# Ethernet2.net
KiCad netlist of a schematic drawn in Altium Designer
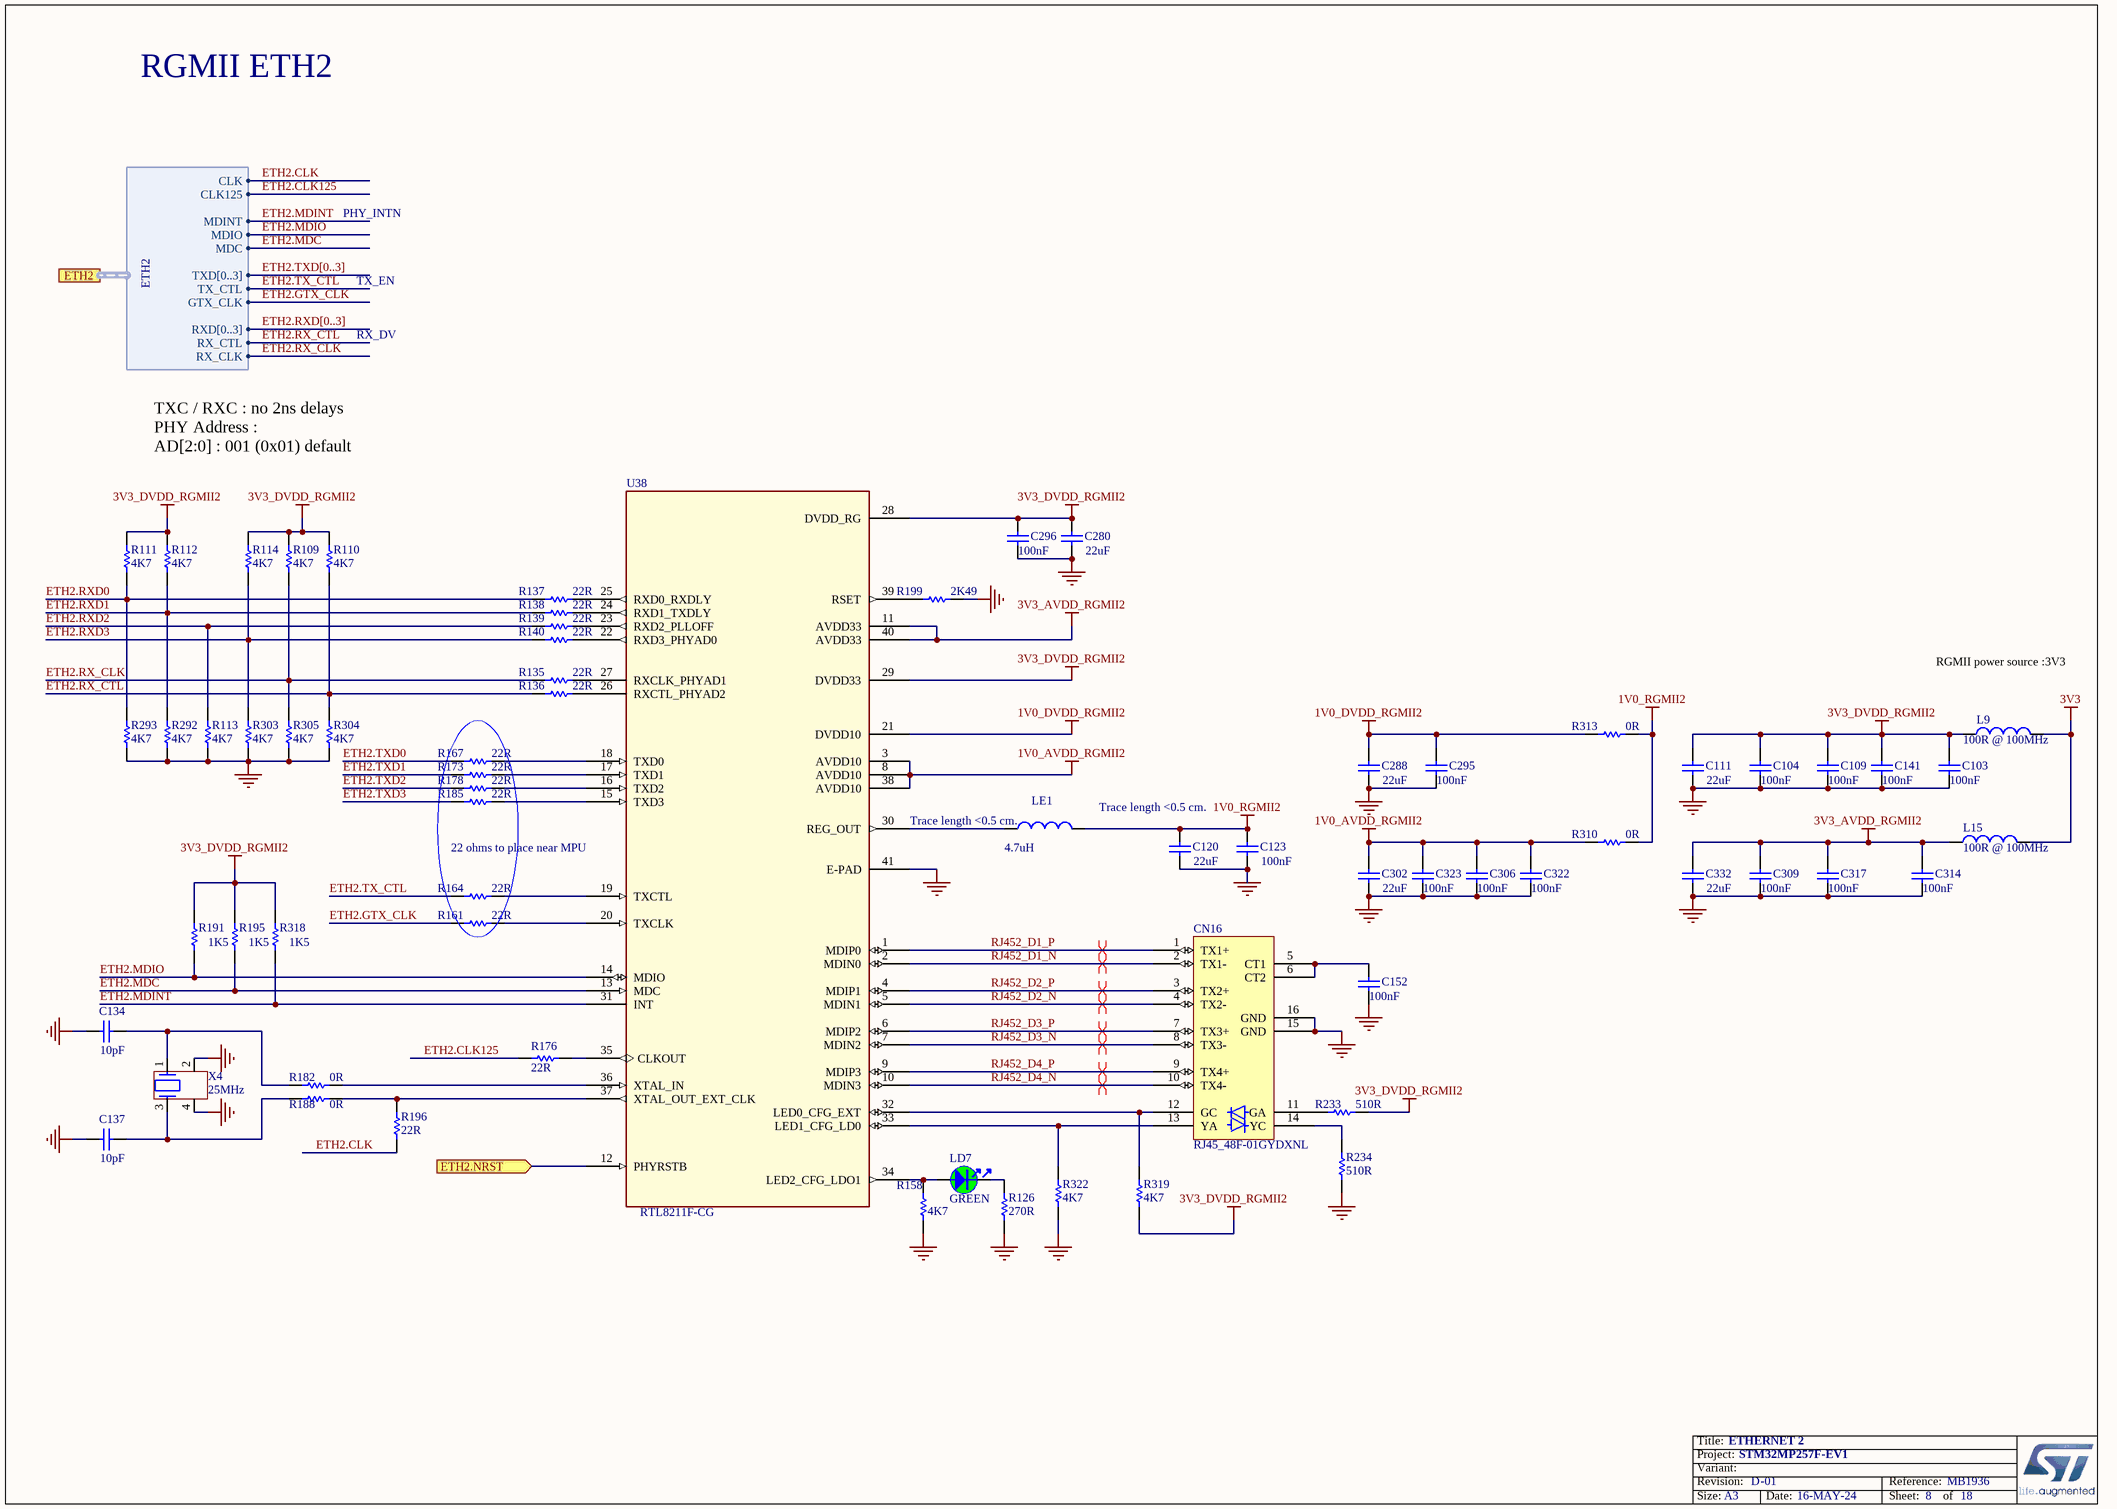
[diagram p0: Ethernet2.SchDoc]

(export (version "E")
  (design (tool "Eeschema 10.0.6"))
  (components
    (comp (ref "C103")
      (value "100nF")
      (footprint "MCD_PARTS:C0402")
      (description "Capacitor,100nF,16V,X7R,10%,0402")
      (fields
        (field (name "INTERNAL_PART_NUMBER") "MCD-00006")
        (field (name "MANUFACTURER_PART_NUMBER") "CC0402KRX7R7BB104")
        (field (name "PROVIDED_BY") "SUBCO")
      )
      (libsource (lib "MCD_PARTS_database") (part "Capacitor"))
    )
    (comp (ref "C104")
      (value "100nF")
      (footprint "MCD_PARTS:C0402")
      (description "Capacitor,100nF,16V,X7R,10%,0402")
      (fields
        (field (name "INTERNAL_PART_NUMBER") "MCD-00006")
        (field (name "MANUFACTURER_PART_NUMBER") "CC0402KRX7R7BB104")
        (field (name "PROVIDED_BY") "SUBCO")
      )
      (libsource (lib "MCD_PARTS_database") (part "Capacitor"))
    )
    (comp (ref "C109")
      (value "100nF")
      (footprint "MCD_PARTS:C0402")
      (description "Capacitor,100nF,16V,X7R,10%,0402")
      (fields
        (field (name "INTERNAL_PART_NUMBER") "MCD-00006")
        (field (name "MANUFACTURER_PART_NUMBER") "CC0402KRX7R7BB104")
        (field (name "PROVIDED_BY") "SUBCO")
      )
      (libsource (lib "MCD_PARTS_database") (part "Capacitor"))
    )
    (comp (ref "C111")
      (value "22uF")
      (footprint "MCD_PARTS:C0603")
      (description "Capacitor,22uF,6V3,X5R,20%,0603")
      (fields
        (field (name "INTERNAL_PART_NUMBER") "MCD-00100")
        (field (name "MANUFACTURER_PART_NUMBER") "GRM188R60J226MEA0J")
        (field (name "PROVIDED_BY") "SUBCO")
      )
      (libsource (lib "MCD_PARTS_database") (part "Capacitor"))
    )
    (comp (ref "C120")
      (value "22uF")
      (footprint "MCD_PARTS:C0603")
      (description "Capacitor,22uF,6V3,X5R,20%,0603")
      (fields
        (field (name "INTERNAL_PART_NUMBER") "MCD-00100")
        (field (name "MANUFACTURER_PART_NUMBER") "GRM188R60J226MEA0J")
        (field (name "PROVIDED_BY") "SUBCO")
      )
      (libsource (lib "MCD_PARTS_database") (part "Capacitor"))
    )
    (comp (ref "C123")
      (value "100nF")
      (footprint "MCD_PARTS:C0402")
      (description "Capacitor,100nF,16V,X7R,10%,0402")
      (fields
        (field (name "INTERNAL_PART_NUMBER") "MCD-00006")
        (field (name "MANUFACTURER_PART_NUMBER") "CC0402KRX7R7BB104")
        (field (name "PROVIDED_BY") "SUBCO")
      )
      (libsource (lib "MCD_PARTS_database") (part "Capacitor"))
    )
    (comp (ref "C134")
      (value "10pF")
      (footprint "MCD_PARTS:C0402")
      (description "Capacitor,10pF,50V,NPO,5%,0402")
      (fields
        (field (name "INTERNAL_PART_NUMBER") "MCD-00015")
        (field (name "MANUFACTURER_PART_NUMBER") "CC0402JRNPO9BN100")
        (field (name "PROVIDED_BY") "SUBCO")
      )
      (libsource (lib "MCD_PARTS_database") (part "Capacitor"))
    )
    (comp (ref "C137")
      (value "10pF")
      (footprint "MCD_PARTS:C0402")
      (description "Capacitor,10pF,50V,NPO,5%,0402")
      (fields
        (field (name "INTERNAL_PART_NUMBER") "MCD-00015")
        (field (name "MANUFACTURER_PART_NUMBER") "CC0402JRNPO9BN100")
        (field (name "PROVIDED_BY") "SUBCO")
      )
      (libsource (lib "MCD_PARTS_database") (part "Capacitor"))
    )
    (comp (ref "C141")
      (value "100nF")
      (footprint "MCD_PARTS:C0402")
      (description "Capacitor,100nF,16V,X7R,10%,0402")
      (fields
        (field (name "INTERNAL_PART_NUMBER") "MCD-00006")
        (field (name "MANUFACTURER_PART_NUMBER") "CC0402KRX7R7BB104")
        (field (name "PROVIDED_BY") "SUBCO")
      )
      (libsource (lib "MCD_PARTS_database") (part "Capacitor"))
    )
    (comp (ref "C152")
      (value "100nF")
      (footprint "MCD_PARTS:C0402")
      (description "Capacitor,100nF,16V,X7R,10%,0402")
      (fields
        (field (name "INTERNAL_PART_NUMBER") "MCD-00006")
        (field (name "MANUFACTURER_PART_NUMBER") "CC0402KRX7R7BB104")
        (field (name "PROVIDED_BY") "SUBCO")
      )
      (libsource (lib "MCD_PARTS_database") (part "Capacitor"))
    )
    (comp (ref "C280")
      (value "22uF")
      (footprint "MCD_PARTS:C0603")
      (description "Capacitor,22uF,6V3,X5R,20%,0603")
      (fields
        (field (name "INTERNAL_PART_NUMBER") "MCD-00100")
        (field (name "MANUFACTURER_PART_NUMBER") "GRM188R60J226MEA0J")
        (field (name "PROVIDED_BY") "SUBCO")
      )
      (libsource (lib "MCD_PARTS_database") (part "Capacitor"))
    )
    (comp (ref "C288")
      (value "22uF")
      (footprint "MCD_PARTS:C0603")
      (description "Capacitor,22uF,6V3,X5R,20%,0603")
      (fields
        (field (name "INTERNAL_PART_NUMBER") "MCD-00100")
        (field (name "MANUFACTURER_PART_NUMBER") "GRM188R60J226MEA0J")
        (field (name "PROVIDED_BY") "SUBCO")
      )
      (libsource (lib "MCD_PARTS_database") (part "Capacitor"))
    )
    (comp (ref "C295")
      (value "100nF")
      (footprint "MCD_PARTS:C0402")
      (description "Capacitor,100nF,16V,X7R,10%,0402")
      (fields
        (field (name "INTERNAL_PART_NUMBER") "MCD-00006")
        (field (name "MANUFACTURER_PART_NUMBER") "CC0402KRX7R7BB104")
        (field (name "PROVIDED_BY") "SUBCO")
      )
      (libsource (lib "MCD_PARTS_database") (part "Capacitor"))
    )
    (comp (ref "C296")
      (value "100nF")
      (footprint "MCD_PARTS:C0402")
      (description "Capacitor,100nF,16V,X7R,10%,0402")
      (fields
        (field (name "INTERNAL_PART_NUMBER") "MCD-00006")
        (field (name "MANUFACTURER_PART_NUMBER") "CC0402KRX7R7BB104")
        (field (name "PROVIDED_BY") "SUBCO")
      )
      (libsource (lib "MCD_PARTS_database") (part "Capacitor"))
    )
    (comp (ref "C302")
      (value "22uF")
      (footprint "MCD_PARTS:C0603")
      (description "Capacitor,22uF,6V3,X5R,20%,0603")
      (fields
        (field (name "INTERNAL_PART_NUMBER") "MCD-00100")
        (field (name "MANUFACTURER_PART_NUMBER") "GRM188R60J226MEA0J")
        (field (name "PROVIDED_BY") "SUBCO")
      )
      (libsource (lib "MCD_PARTS_database") (part "Capacitor"))
    )
    (comp (ref "C306")
      (value "100nF")
      (footprint "MCD_PARTS:C0402")
      (description "Capacitor,100nF,16V,X7R,10%,0402")
      (fields
        (field (name "INTERNAL_PART_NUMBER") "MCD-00006")
        (field (name "MANUFACTURER_PART_NUMBER") "CC0402KRX7R7BB104")
        (field (name "PROVIDED_BY") "SUBCO")
      )
      (libsource (lib "MCD_PARTS_database") (part "Capacitor"))
    )
    (comp (ref "C309")
      (value "100nF")
      (footprint "MCD_PARTS:C0402")
      (description "Capacitor,100nF,16V,X7R,10%,0402")
      (fields
        (field (name "INTERNAL_PART_NUMBER") "MCD-00006")
        (field (name "MANUFACTURER_PART_NUMBER") "CC0402KRX7R7BB104")
        (field (name "PROVIDED_BY") "SUBCO")
      )
      (libsource (lib "MCD_PARTS_database") (part "Capacitor"))
    )
    (comp (ref "C314")
      (value "100nF")
      (footprint "MCD_PARTS:C0402")
      (description "Capacitor,100nF,16V,X7R,10%,0402")
      (fields
        (field (name "INTERNAL_PART_NUMBER") "MCD-00006")
        (field (name "MANUFACTURER_PART_NUMBER") "CC0402KRX7R7BB104")
        (field (name "PROVIDED_BY") "SUBCO")
      )
      (libsource (lib "MCD_PARTS_database") (part "Capacitor"))
    )
    (comp (ref "C317")
      (value "100nF")
      (footprint "MCD_PARTS:C0402")
      (description "Capacitor,100nF,16V,X7R,10%,0402")
      (fields
        (field (name "INTERNAL_PART_NUMBER") "MCD-00006")
        (field (name "MANUFACTURER_PART_NUMBER") "CC0402KRX7R7BB104")
        (field (name "PROVIDED_BY") "SUBCO")
      )
      (libsource (lib "MCD_PARTS_database") (part "Capacitor"))
    )
    (comp (ref "C322")
      (value "100nF")
      (footprint "MCD_PARTS:C0402")
      (description "Capacitor,100nF,16V,X7R,10%,0402")
      (fields
        (field (name "INTERNAL_PART_NUMBER") "MCD-00006")
        (field (name "MANUFACTURER_PART_NUMBER") "CC0402KRX7R7BB104")
        (field (name "PROVIDED_BY") "SUBCO")
      )
      (libsource (lib "MCD_PARTS_database") (part "Capacitor"))
    )
    (comp (ref "C323")
      (value "100nF")
      (footprint "MCD_PARTS:C0402")
      (description "Capacitor,100nF,16V,X7R,10%,0402")
      (fields
        (field (name "INTERNAL_PART_NUMBER") "MCD-00006")
        (field (name "MANUFACTURER_PART_NUMBER") "CC0402KRX7R7BB104")
        (field (name "PROVIDED_BY") "SUBCO")
      )
      (libsource (lib "MCD_PARTS_database") (part "Capacitor"))
    )
    (comp (ref "C332")
      (value "22uF")
      (footprint "MCD_PARTS:C0603")
      (description "Capacitor,22uF,6V3,X5R,20%,0603")
      (fields
        (field (name "INTERNAL_PART_NUMBER") "MCD-00100")
        (field (name "MANUFACTURER_PART_NUMBER") "GRM188R60J226MEA0J")
        (field (name "PROVIDED_BY") "SUBCO")
      )
      (libsource (lib "MCD_PARTS_database") (part "Capacitor"))
    )
    (comp (ref "CN16")
      (value "RJ45_48F-01GYDXNL")
      (footprint "MCD_PARTS:CON_RJ45_YD_48F-01GYDXNL_LED-P")
      (description "Connector_RJ45, led pull down, T= 13.84mm")
      (fields
        (field (name "INTERNAL_PART_NUMBER") "MCD-01129")
        (field (name "MANUFACTURER_PART_NUMBER") "48F-01GYDXNL")
      )
      (libsource (lib "MCD_PARTS_database") (part "RJ45_48F_01GYDXNL_LPD"))
    )
    (comp (ref "L9")
      (value "100R @ 100MHz")
      (footprint "MCD_PARTS:FIL_0603_H0P65")
      (description "Ferrite bead 100R 2A 0603")
      (fields
        (field (name "INTERNAL_PART_NUMBER") "MCD-00094")
        (field (name "MANUFACTURER_PART_NUMBER") "BLM18EG101TN1")
        (field (name "PROVIDED_BY") "SUBCO")
      )
      (libsource (lib "MCD_PARTS_database") (part "BEAD"))
    )
    (comp (ref "L15")
      (value "100R @ 100MHz")
      (footprint "MCD_PARTS:FIL_0603_H0P65")
      (description "Ferrite bead 100R 2A 0603")
      (fields
        (field (name "INTERNAL_PART_NUMBER") "MCD-00094")
        (field (name "MANUFACTURER_PART_NUMBER") "BLM18EG101TN1")
        (field (name "PROVIDED_BY") "SUBCO")
      )
      (libsource (lib "MCD_PARTS_database") (part "BEAD"))
    )
    (comp (ref "LD7")
      (value "GREEN")
      (footprint "MCD_PARTS:LED_0603_OSRAM_LG-Q396-PS-35_GREEN_1A2K_H0P4")
      (description "LED Green, 0603 SMD, Forward Voltage Typ=2V, Max=2.5V")
      (fields
        (field (name "INTERNAL_PART_NUMBER") "MCD-00588")
        (field (name "MANUFACTURER_PART_NUMBER") "LG Q396-PS-35")
        (field (name "PROVIDED_BY") "SUBCO")
      )
      (libsource (lib "MCD_PARTS_database") (part "LED_green"))
    )
    (comp (ref "LE1")
      (value "4.7uH")
      (footprint "MCD_PARTS:L1210_LQH")
      (description "FIXED IND 4.7UH 1A 180 MOHM 30% SMD")
      (fields
        (field (name "INTERNAL_PART_NUMBER") "MCD-00048")
        (field (name "MANUFACTURER_PART_NUMBER") "LQH32PN4R7NN0L")
        (field (name "PROVIDED_BY") "SUBCO")
      )
      (libsource (lib "MCD_PARTS_database") (part "Inductor"))
    )
    (comp (ref "R109")
      (value "4K7")
      (footprint "MCD_PARTS:R0402")
      (description "Resistor,4K7,0402,1%,1/16W")
      (fields
        (field (name "INTERNAL_PART_NUMBER") "MCD-00065")
        (field (name "MANUFACTURER_PART_NUMBER") "RC0402FR-074K7L")
        (field (name "PROVIDED_BY") "SUBCO")
      )
      (libsource (lib "MCD_PARTS_database") (part "Resistor"))
    )
    (comp (ref "R110")
      (value "4K7")
      (footprint "MCD_PARTS:R0402")
      (description "Resistor,4K7,0402,1%,1/16W")
      (fields
        (field (name "INTERNAL_PART_NUMBER") "MCD-00065")
        (field (name "MANUFACTURER_PART_NUMBER") "RC0402FR-074K7L")
        (field (name "PROVIDED_BY") "SUBCO")
      )
      (libsource (lib "MCD_PARTS_database") (part "Resistor"))
    )
    (comp (ref "R111")
      (value "4K7")
      (footprint "MCD_PARTS:R0402")
      (description "Resistor,4K7,0402,1%,1/16W")
      (fields
        (field (name "INTERNAL_PART_NUMBER") "MCD-00065")
        (field (name "MANUFACTURER_PART_NUMBER") "RC0402FR-074K7L")
        (field (name "PROVIDED_BY") "SUBCO")
      )
      (libsource (lib "MCD_PARTS_database") (part "Resistor"))
    )
    (comp (ref "R112")
      (value "4K7")
      (footprint "MCD_PARTS:R0402")
      (description "Resistor,4K7,0402,1%,1/16W")
      (fields
        (field (name "INTERNAL_PART_NUMBER") "MCD-00065")
        (field (name "MANUFACTURER_PART_NUMBER") "RC0402FR-074K7L")
        (field (name "PROVIDED_BY") "SUBCO")
      )
      (libsource (lib "MCD_PARTS_database") (part "Resistor"))
    )
    (comp (ref "R113")
      (value "4K7")
      (footprint "MCD_PARTS:R0402")
      (description "Resistor,4K7,0402,1%,1/16W")
      (fields
        (field (name "INTERNAL_PART_NUMBER") "MCD-00065")
        (field (name "MANUFACTURER_PART_NUMBER") "RC0402FR-074K7L")
        (field (name "PROVIDED_BY") "SUBCO")
      )
      (libsource (lib "MCD_PARTS_database") (part "Resistor"))
    )
    (comp (ref "R114")
      (value "4K7")
      (footprint "MCD_PARTS:R0402")
      (description "Resistor,4K7,0402,1%,1/16W")
      (fields
        (field (name "INTERNAL_PART_NUMBER") "MCD-00065")
        (field (name "MANUFACTURER_PART_NUMBER") "RC0402FR-074K7L")
        (field (name "PROVIDED_BY") "SUBCO")
      )
      (libsource (lib "MCD_PARTS_database") (part "Resistor"))
    )
    (comp (ref "R126")
      (value "270R")
      (footprint "MCD_PARTS:R0402")
      (description "Resistor,270R,0402,1%,1/16W")
      (fields
        (field (name "INTERNAL_PART_NUMBER") "MCD-00441")
        (field (name "MANUFACTURER_PART_NUMBER") "RC0402FR-07270RL")
        (field (name "PROVIDED_BY") "SUBCO")
      )
      (libsource (lib "MCD_PARTS_database") (part "Resistor"))
    )
    (comp (ref "R135")
      (value "22R")
      (footprint "MCD_PARTS:R0201_H0P23")
      (description "Resistor, 22R, 0201, +/-1%, 1/20W")
      (fields
        (field (name "INTERNAL_PART_NUMBER") "MCD-02978")
        (field (name "MANUFACTURER_PART_NUMBER") "RC0201FR-0722RL")
      )
      (libsource (lib "MCD_PARTS_database") (part "Resistor"))
    )
    (comp (ref "R136")
      (value "22R")
      (footprint "MCD_PARTS:R0201_H0P23")
      (description "Resistor, 22R, 0201, +/-1%, 1/20W")
      (fields
        (field (name "INTERNAL_PART_NUMBER") "MCD-02978")
        (field (name "MANUFACTURER_PART_NUMBER") "RC0201FR-0722RL")
      )
      (libsource (lib "MCD_PARTS_database") (part "Resistor"))
    )
    (comp (ref "R137")
      (value "22R")
      (footprint "MCD_PARTS:R0201_H0P23")
      (description "Resistor, 22R, 0201, +/-1%, 1/20W")
      (fields
        (field (name "INTERNAL_PART_NUMBER") "MCD-02978")
        (field (name "MANUFACTURER_PART_NUMBER") "RC0201FR-0722RL")
      )
      (libsource (lib "MCD_PARTS_database") (part "Resistor"))
    )
    (comp (ref "R138")
      (value "22R")
      (footprint "MCD_PARTS:R0201_H0P23")
      (description "Resistor, 22R, 0201, +/-1%, 1/20W")
      (fields
        (field (name "INTERNAL_PART_NUMBER") "MCD-02978")
        (field (name "MANUFACTURER_PART_NUMBER") "RC0201FR-0722RL")
      )
      (libsource (lib "MCD_PARTS_database") (part "Resistor"))
    )
    (comp (ref "R139")
      (value "22R")
      (footprint "MCD_PARTS:R0201_H0P23")
      (description "Resistor, 22R, 0201, +/-1%, 1/20W")
      (fields
        (field (name "INTERNAL_PART_NUMBER") "MCD-02978")
        (field (name "MANUFACTURER_PART_NUMBER") "RC0201FR-0722RL")
      )
      (libsource (lib "MCD_PARTS_database") (part "Resistor"))
    )
    (comp (ref "R140")
      (value "22R")
      (footprint "MCD_PARTS:R0201_H0P23")
      (description "Resistor, 22R, 0201, +/-1%, 1/20W")
      (fields
        (field (name "INTERNAL_PART_NUMBER") "MCD-02978")
        (field (name "MANUFACTURER_PART_NUMBER") "RC0201FR-0722RL")
      )
      (libsource (lib "MCD_PARTS_database") (part "Resistor"))
    )
    (comp (ref "R158")
      (value "4K7")
      (footprint "MCD_PARTS:R0402")
      (description "Resistor,4K7,0402,1%,1/16W")
      (fields
        (field (name "INTERNAL_PART_NUMBER") "MCD-00065")
        (field (name "MANUFACTURER_PART_NUMBER") "RC0402FR-074K7L")
        (field (name "PROVIDED_BY") "SUBCO")
      )
      (libsource (lib "MCD_PARTS_database") (part "Resistor"))
    )
    (comp (ref "R161")
      (value "22R")
      (footprint "MCD_PARTS:R0201_H0P23")
      (description "Resistor, 22R, 0201, +/-1%, 1/20W")
      (fields
        (field (name "INTERNAL_PART_NUMBER") "MCD-02978")
        (field (name "MANUFACTURER_PART_NUMBER") "RC0201FR-0722RL")
      )
      (libsource (lib "MCD_PARTS_database") (part "Resistor"))
    )
    (comp (ref "R164")
      (value "22R")
      (footprint "MCD_PARTS:R0201_H0P23")
      (description "Resistor, 22R, 0201, +/-1%, 1/20W")
      (fields
        (field (name "INTERNAL_PART_NUMBER") "MCD-02978")
        (field (name "MANUFACTURER_PART_NUMBER") "RC0201FR-0722RL")
      )
      (libsource (lib "MCD_PARTS_database") (part "Resistor"))
    )
    (comp (ref "R167")
      (value "22R")
      (footprint "MCD_PARTS:R0201_H0P23")
      (description "Resistor, 22R, 0201, +/-1%, 1/20W")
      (fields
        (field (name "INTERNAL_PART_NUMBER") "MCD-02978")
        (field (name "MANUFACTURER_PART_NUMBER") "RC0201FR-0722RL")
      )
      (libsource (lib "MCD_PARTS_database") (part "Resistor"))
    )
    (comp (ref "R173")
      (value "22R")
      (footprint "MCD_PARTS:R0201_H0P23")
      (description "Resistor, 22R, 0201, +/-1%, 1/20W")
      (fields
        (field (name "INTERNAL_PART_NUMBER") "MCD-02978")
        (field (name "MANUFACTURER_PART_NUMBER") "RC0201FR-0722RL")
      )
      (libsource (lib "MCD_PARTS_database") (part "Resistor"))
    )
    (comp (ref "R176")
      (value "22R")
      (footprint "MCD_PARTS:R0201_H0P23")
      (description "Resistor, 22R, 0201, +/-1%, 1/20W")
      (fields
        (field (name "INTERNAL_PART_NUMBER") "MCD-02978")
        (field (name "MANUFACTURER_PART_NUMBER") "RC0201FR-0722RL")
      )
      (libsource (lib "MCD_PARTS_database") (part "Resistor"))
    )
    (comp (ref "R178")
      (value "22R")
      (footprint "MCD_PARTS:R0201_H0P23")
      (description "Resistor, 22R, 0201, +/-1%, 1/20W")
      (fields
        (field (name "INTERNAL_PART_NUMBER") "MCD-02978")
        (field (name "MANUFACTURER_PART_NUMBER") "RC0201FR-0722RL")
      )
      (libsource (lib "MCD_PARTS_database") (part "Resistor"))
    )
    (comp (ref "R182")
      (value "0R")
      (footprint "MCD_PARTS:R0402")
      (description "Resistor,0R,0402,5%,1/16W")
      (fields
        (field (name "INTERNAL_PART_NUMBER") "MCD-00052")
        (field (name "MANUFACTURER_PART_NUMBER") "RC0402JR-070RL")
        (field (name "PROVIDED_BY") "SUBCO")
      )
      (libsource (lib "MCD_PARTS_database") (part "Resistor"))
    )
    (comp (ref "R185")
      (value "22R")
      (footprint "MCD_PARTS:R0201_H0P23")
      (description "Resistor, 22R, 0201, +/-1%, 1/20W")
      (fields
        (field (name "INTERNAL_PART_NUMBER") "MCD-02978")
        (field (name "MANUFACTURER_PART_NUMBER") "RC0201FR-0722RL")
      )
      (libsource (lib "MCD_PARTS_database") (part "Resistor"))
    )
    (comp (ref "R188")
      (value "0R")
      (footprint "MCD_PARTS:R0402")
      (description "Resistor,0R,0402,5%,1/16W")
      (fields
        (field (name "INTERNAL_PART_NUMBER") "MCD-00052")
        (field (name "MANUFACTURER_PART_NUMBER") "RC0402JR-070RL")
        (field (name "PROVIDED_BY") "SUBCO")
      )
      (libsource (lib "MCD_PARTS_database") (part "Resistor"))
    )
    (comp (ref "R191")
      (value "1K5")
      (footprint "MCD_PARTS:R0402")
      (description "Resistor,1K5,0402,1%,1/16W")
      (fields
        (field (name "INTERNAL_PART_NUMBER") "MCD-00068")
        (field (name "MANUFACTURER_PART_NUMBER") "RC0402FR-071K5L")
        (field (name "PROVIDED_BY") "SUBCO")
      )
      (libsource (lib "MCD_PARTS_database") (part "Resistor"))
    )
    (comp (ref "R195")
      (value "1K5")
      (footprint "MCD_PARTS:R0402")
      (description "Resistor,1K5,0402,1%,1/16W")
      (fields
        (field (name "INTERNAL_PART_NUMBER") "MCD-00068")
        (field (name "MANUFACTURER_PART_NUMBER") "RC0402FR-071K5L")
        (field (name "PROVIDED_BY") "SUBCO")
      )
      (libsource (lib "MCD_PARTS_database") (part "Resistor"))
    )
    (comp (ref "R196")
      (value "22R")
      (footprint "MCD_PARTS:R0201_H0P23")
      (description "Resistor, 22R, 0201, +/-1%, 1/20W")
      (fields
        (field (name "INTERNAL_PART_NUMBER") "MCD-02978")
        (field (name "MANUFACTURER_PART_NUMBER") "RC0201FR-0722RL")
      )
      (libsource (lib "MCD_PARTS_database") (part "Resistor"))
    )
    (comp (ref "R199")
      (value "2K49")
      (footprint "MCD_PARTS:R0402")
      (description "Resistor,2K49,0402,1%,1/16W")
      (fields
        (field (name "INTERNAL_PART_NUMBER") "MCD-00183")
        (field (name "MANUFACTURER_PART_NUMBER") "RC0402FR-072K49L")
        (field (name "PROVIDED_BY") "SUBCO")
      )
      (libsource (lib "MCD_PARTS_database") (part "Resistor"))
    )
    (comp (ref "R233")
      (value "510R")
      (footprint "MCD_PARTS:R0402")
      (description "Resistor,510R,0402,1%,1/16W")
      (fields
        (field (name "INTERNAL_PART_NUMBER") "MCD-00064")
        (field (name "MANUFACTURER_PART_NUMBER") "RC0402FR-07510RL")
        (field (name "PROVIDED_BY") "SUBCO")
      )
      (libsource (lib "MCD_PARTS_database") (part "Resistor"))
    )
    (comp (ref "R234")
      (value "510R")
      (footprint "MCD_PARTS:R0402")
      (description "Resistor,510R,0402,1%,1/16W")
      (fields
        (field (name "INTERNAL_PART_NUMBER") "MCD-00064")
        (field (name "MANUFACTURER_PART_NUMBER") "RC0402FR-07510RL")
        (field (name "PROVIDED_BY") "SUBCO")
      )
      (libsource (lib "MCD_PARTS_database") (part "Resistor"))
    )
    (comp (ref "R292")
      (value "4K7")
      (footprint "MCD_PARTS:R0402")
      (description "Resistor,4K7,0402,1%,1/16W")
      (fields
        (field (name "INTERNAL_PART_NUMBER") "MCD-00065")
        (field (name "MANUFACTURER_PART_NUMBER") "RC0402FR-074K7L")
        (field (name "PROVIDED_BY") "SUBCO")
      )
      (libsource (lib "MCD_PARTS_database") (part "Resistor"))
    )
    (comp (ref "R293")
      (value "4K7")
      (footprint "MCD_PARTS:R0402")
      (description "Resistor,4K7,0402,1%,1/16W")
      (fields
        (field (name "INTERNAL_PART_NUMBER") "MCD-00065")
        (field (name "MANUFACTURER_PART_NUMBER") "RC0402FR-074K7L")
        (field (name "PROVIDED_BY") "SUBCO")
      )
      (libsource (lib "MCD_PARTS_database") (part "Resistor"))
    )
    (comp (ref "R303")
      (value "4K7")
      (footprint "MCD_PARTS:R0402")
      (description "Resistor,4K7,0402,1%,1/16W")
      (fields
        (field (name "INTERNAL_PART_NUMBER") "MCD-00065")
        (field (name "MANUFACTURER_PART_NUMBER") "RC0402FR-074K7L")
        (field (name "PROVIDED_BY") "SUBCO")
      )
      (libsource (lib "MCD_PARTS_database") (part "Resistor"))
    )
    (comp (ref "R304")
      (value "4K7")
      (footprint "MCD_PARTS:R0402")
      (description "Resistor,4K7,0402,1%,1/16W")
      (fields
        (field (name "INTERNAL_PART_NUMBER") "MCD-00065")
        (field (name "MANUFACTURER_PART_NUMBER") "RC0402FR-074K7L")
        (field (name "PROVIDED_BY") "SUBCO")
      )
      (libsource (lib "MCD_PARTS_database") (part "Resistor"))
    )
    (comp (ref "R305")
      (value "4K7")
      (footprint "MCD_PARTS:R0402")
      (description "Resistor,4K7,0402,1%,1/16W")
      (fields
        (field (name "INTERNAL_PART_NUMBER") "MCD-00065")
        (field (name "MANUFACTURER_PART_NUMBER") "RC0402FR-074K7L")
        (field (name "PROVIDED_BY") "SUBCO")
      )
      (libsource (lib "MCD_PARTS_database") (part "Resistor"))
    )
    (comp (ref "R310")
      (value "0R")
      (footprint "MCD_PARTS:R0603")
      (description "Resistor,0R,0603,5%,1/10W")
      (fields
        (field (name "INTERNAL_PART_NUMBER") "MCD-00056")
        (field (name "MANUFACTURER_PART_NUMBER") "RC0603JR-070RL")
        (field (name "PROVIDED_BY") "SUBCO")
      )
      (libsource (lib "MCD_PARTS_database") (part "Resistor"))
    )
    (comp (ref "R313")
      (value "0R")
      (footprint "MCD_PARTS:R0603")
      (description "Resistor,0R,0603,5%,1/10W")
      (fields
        (field (name "INTERNAL_PART_NUMBER") "MCD-00056")
        (field (name "MANUFACTURER_PART_NUMBER") "RC0603JR-070RL")
        (field (name "PROVIDED_BY") "SUBCO")
      )
      (libsource (lib "MCD_PARTS_database") (part "Resistor"))
    )
    (comp (ref "R318")
      (value "1K5")
      (footprint "MCD_PARTS:R0402")
      (description "Resistor,1K5,0402,1%,1/16W")
      (fields
        (field (name "INTERNAL_PART_NUMBER") "MCD-00068")
        (field (name "MANUFACTURER_PART_NUMBER") "RC0402FR-071K5L")
        (field (name "PROVIDED_BY") "SUBCO")
      )
      (libsource (lib "MCD_PARTS_database") (part "Resistor"))
    )
    (comp (ref "R319")
      (value "4K7")
      (footprint "MCD_PARTS:R0402")
      (description "Resistor,4K7,0402,1%,1/16W")
      (fields
        (field (name "INTERNAL_PART_NUMBER") "MCD-00065")
        (field (name "MANUFACTURER_PART_NUMBER") "RC0402FR-074K7L")
        (field (name "PROVIDED_BY") "SUBCO")
      )
      (libsource (lib "MCD_PARTS_database") (part "Resistor"))
    )
    (comp (ref "R322")
      (value "4K7")
      (footprint "MCD_PARTS:R0402")
      (description "Resistor,4K7,0402,1%,1/16W")
      (fields
        (field (name "INTERNAL_PART_NUMBER") "MCD-00065")
        (field (name "MANUFACTURER_PART_NUMBER") "RC0402FR-074K7L")
        (field (name "PROVIDED_BY") "SUBCO")
      )
      (libsource (lib "MCD_PARTS_database") (part "Resistor"))
    )
    (comp (ref "U38")
      (value "RTL8211F-CG")
      (footprint "MCD_PARTS:ICC_QFN40-EPAD_5X5_P040")
      (description "10/100/1000M GIGABIT Ethernet Transceiver, QFN40 , SMPS version")
      (fields
        (field (name "INTERNAL_PART_NUMBER") "MCD-01130")
        (field (name "MANUFACTURER") "REALTEK")
        (field (name "PROVIDED_BY") "SUBCO")
      )
      (libsource (lib "MCD_PARTS_database") (part "RTL8211F-CG"))
    )
    (comp (ref "X4")
      (value "25MHz")
      (footprint "MCD_PARTS:CRY_NX3225HA_4P")
      (description "Crystal 25Mhz, 10pF, -+50PPM, SMD")
      (fields
        (field (name "INTERNAL_PART_NUMBER") "MCD-01463")
        (field (name "MANUFACTURER_PART_NUMBER") "NX3225GA-25MHZ-EXS00A-CG06750")
        (field (name "PROVIDED_BY") "SUBCO")
      )
      (libsource (lib "MCD_PARTS_database") (part "XTAL_4_PINS"))
    )
  )
  (nets
    (net (code "2") (name "/ETH2.CLK") (class "Default")
      (node (ref "R196") (pin "1") (pinfunction "1_1") (pintype "passive"))
    )
    (net (code "3") (name "/ETH2.CLK125") (class "Default")
      (node (ref "R176") (pin "1") (pinfunction "1_1") (pintype "passive"))
    )
    (net (code "4") (name "/ETH2.GTX_CLK") (class "Default")
      (node (ref "R161") (pin "1") (pinfunction "1_1") (pintype "passive"))
    )
    (net (code "5") (name "/ETH2.MDC") (class "Default")
      (node (ref "R195") (pin "1") (pinfunction "1_1") (pintype "passive"))
      (node (ref "U38") (pin "13") (pinfunction "MDC_13") (pintype "input"))
    )
    (net (code "6") (name "/ETH2.MDINT") (class "Default")
      (node (ref "R318") (pin "1") (pinfunction "1_1") (pintype "passive"))
      (node (ref "U38") (pin "31") (pinfunction "INT_31") (pintype "passive"))
    )
    (net (code "7") (name "/ETH2.MDIO") (class "Default")
      (node (ref "R191") (pin "1") (pinfunction "1_1") (pintype "passive"))
      (node (ref "U38") (pin "14") (pinfunction "MDIO_14") (pintype "bidirectional"))
    )
    (net (code "8") (name "/ETH2.NRST") (class "Default")
      (node (ref "U38") (pin "12") (pinfunction "PHYRSTB_12") (pintype "input"))
    )
    (net (code "9") (name "/ETH2.RXD0") (class "Default")
      (node (ref "R111") (pin "1") (pinfunction "1_1") (pintype "passive"))
      (node (ref "R137") (pin "1") (pinfunction "1_1") (pintype "passive"))
      (node (ref "R293") (pin "2") (pinfunction "2_2") (pintype "passive"))
    )
    (net (code "10") (name "/ETH2.RXD1") (class "Default")
      (node (ref "R112") (pin "1") (pinfunction "1_1") (pintype "passive"))
      (node (ref "R138") (pin "1") (pinfunction "1_1") (pintype "passive"))
      (node (ref "R292") (pin "2") (pinfunction "2_2") (pintype "passive"))
    )
    (net (code "11") (name "/ETH2.RXD2") (class "Default")
      (node (ref "R113") (pin "2") (pinfunction "2_2") (pintype "passive"))
      (node (ref "R139") (pin "1") (pinfunction "1_1") (pintype "passive"))
    )
    (net (code "12") (name "/ETH2.RXD3") (class "Default")
      (node (ref "R114") (pin "1") (pinfunction "1_1") (pintype "passive"))
      (node (ref "R140") (pin "1") (pinfunction "1_1") (pintype "passive"))
      (node (ref "R303") (pin "2") (pinfunction "2_2") (pintype "passive"))
    )
    (net (code "13") (name "/ETH2.RX_CLK") (class "Default")
      (node (ref "R109") (pin "1") (pinfunction "1_1") (pintype "passive"))
      (node (ref "R135") (pin "1") (pinfunction "1_1") (pintype "passive"))
      (node (ref "R305") (pin "2") (pinfunction "2_2") (pintype "passive"))
    )
    (net (code "14") (name "/ETH2.RX_CTL") (class "Default")
      (node (ref "R110") (pin "1") (pinfunction "1_1") (pintype "passive"))
      (node (ref "R136") (pin "1") (pinfunction "1_1") (pintype "passive"))
      (node (ref "R304") (pin "2") (pinfunction "2_2") (pintype "passive"))
    )
    (net (code "15") (name "/ETH2.TXD0") (class "Default")
      (node (ref "R167") (pin "1") (pinfunction "1_1") (pintype "passive"))
    )
    (net (code "16") (name "/ETH2.TXD1") (class "Default")
      (node (ref "R173") (pin "1") (pinfunction "1_1") (pintype "passive"))
    )
    (net (code "17") (name "/ETH2.TXD2") (class "Default")
      (node (ref "R178") (pin "1") (pinfunction "1_1") (pintype "passive"))
    )
    (net (code "18") (name "/ETH2.TXD3") (class "Default")
      (node (ref "R185") (pin "1") (pinfunction "1_1") (pintype "passive"))
    )
    (net (code "20") (name "/ETH2.TX_CTL") (class "Default")
      (node (ref "R164") (pin "1") (pinfunction "1_1") (pintype "passive"))
    )
    (net (code "22") (name "/RJ452_D1_N") (class "Default")
      (node (ref "CN16") (pin "2") (pinfunction "TX1-_2") (pintype "bidirectional"))
      (node (ref "U38") (pin "2") (pinfunction "MDIN0_2") (pintype "bidirectional"))
    )
    (net (code "23") (name "/RJ452_D1_P") (class "Default")
      (node (ref "CN16") (pin "1") (pinfunction "TX1+_1") (pintype "bidirectional"))
      (node (ref "U38") (pin "1") (pinfunction "MDIP0_1") (pintype "bidirectional"))
    )
    (net (code "24") (name "/RJ452_D2_N") (class "Default")
      (node (ref "CN16") (pin "4") (pinfunction "TX2-_4") (pintype "bidirectional"))
      (node (ref "U38") (pin "5") (pinfunction "MDIN1_5") (pintype "bidirectional"))
    )
    (net (code "25") (name "/RJ452_D2_P") (class "Default")
      (node (ref "CN16") (pin "3") (pinfunction "TX2+_3") (pintype "bidirectional"))
      (node (ref "U38") (pin "4") (pinfunction "MDIP1_4") (pintype "bidirectional"))
    )
    (net (code "26") (name "/RJ452_D3_N") (class "Default")
      (node (ref "CN16") (pin "8") (pinfunction "TX3-_8") (pintype "bidirectional"))
      (node (ref "U38") (pin "7") (pinfunction "MDIN2_7") (pintype "bidirectional"))
    )
    (net (code "27") (name "/RJ452_D3_P") (class "Default")
      (node (ref "CN16") (pin "7") (pinfunction "TX3+_7") (pintype "bidirectional"))
      (node (ref "U38") (pin "6") (pinfunction "MDIP2_6") (pintype "bidirectional"))
    )
    (net (code "28") (name "/RJ452_D4_N") (class "Default")
      (node (ref "CN16") (pin "10") (pinfunction "TX4-_10") (pintype "bidirectional"))
      (node (ref "U38") (pin "10") (pinfunction "MDIN3_10") (pintype "bidirectional"))
    )
    (net (code "29") (name "/RJ452_D4_P") (class "Default")
      (node (ref "CN16") (pin "9") (pinfunction "TX4+_9") (pintype "bidirectional"))
      (node (ref "U38") (pin "9") (pinfunction "MDIP3_9") (pintype "bidirectional"))
    )
    (net (code "31") (name "1V0_AVDD_RGMII2") (class "Default")
      (node (ref "C302") (pin "2") (pinfunction "2_2") (pintype "passive"))
      (node (ref "C306") (pin "2") (pinfunction "2_2") (pintype "passive"))
      (node (ref "C322") (pin "2") (pinfunction "2_2") (pintype "passive"))
      (node (ref "C323") (pin "2") (pinfunction "2_2") (pintype "passive"))
      (node (ref "R310") (pin "1") (pinfunction "1_1") (pintype "passive"))
      (node (ref "U38") (pin "3") (pinfunction "AVDD10_3") (pintype "power_in"))
      (node (ref "U38") (pin "38") (pinfunction "AVDD10_38") (pintype "power_in"))
      (node (ref "U38") (pin "8") (pinfunction "AVDD10_8") (pintype "power_in"))
    )
    (net (code "32") (name "1V0_DVDD_RGMII2") (class "Default")
      (node (ref "C288") (pin "2") (pinfunction "2_2") (pintype "passive"))
      (node (ref "C295") (pin "2") (pinfunction "2_2") (pintype "passive"))
      (node (ref "R313") (pin "1") (pinfunction "1_1") (pintype "passive"))
      (node (ref "U38") (pin "21") (pinfunction "DVDD10_21") (pintype "power_in"))
    )
    (net (code "33") (name "1V0_RGMII2") (class "Default")
      (node (ref "C120") (pin "2") (pinfunction "2_2") (pintype "passive"))
      (node (ref "C123") (pin "2") (pinfunction "2_2") (pintype "passive"))
      (node (ref "LE1") (pin "2") (pinfunction "2_2") (pintype "passive"))
      (node (ref "R310") (pin "2") (pinfunction "2_2") (pintype "passive"))
      (node (ref "R313") (pin "2") (pinfunction "2_2") (pintype "passive"))
    )
    (net (code "34") (name "3V3") (class "Default")
      (node (ref "L15") (pin "2") (pinfunction "2_2") (pintype "passive"))
      (node (ref "L9") (pin "2") (pinfunction "2_2") (pintype "passive"))
    )
    (net (code "35") (name "3V3_AVDD_RGMII2") (class "Default")
      (node (ref "C309") (pin "2") (pinfunction "2_2") (pintype "passive"))
      (node (ref "C314") (pin "2") (pinfunction "2_2") (pintype "passive"))
      (node (ref "C317") (pin "2") (pinfunction "2_2") (pintype "passive"))
      (node (ref "C332") (pin "2") (pinfunction "2_2") (pintype "passive"))
      (node (ref "L15") (pin "1") (pinfunction "1_1") (pintype "passive"))
      (node (ref "U38") (pin "11") (pinfunction "AVDD33_11") (pintype "power_in"))
      (node (ref "U38") (pin "40") (pinfunction "AVDD33_40") (pintype "power_in"))
    )
    (net (code "36") (name "3V3_DVDD_RGMII2") (class "Default")
      (node (ref "C103") (pin "2") (pinfunction "2_2") (pintype "passive"))
      (node (ref "C104") (pin "2") (pinfunction "2_2") (pintype "passive"))
      (node (ref "C109") (pin "2") (pinfunction "2_2") (pintype "passive"))
      (node (ref "C111") (pin "2") (pinfunction "2_2") (pintype "passive"))
      (node (ref "C141") (pin "2") (pinfunction "2_2") (pintype "passive"))
      (node (ref "C280") (pin "1") (pinfunction "1_1") (pintype "passive"))
      (node (ref "C296") (pin "2") (pinfunction "2_2") (pintype "passive"))
      (node (ref "L9") (pin "1") (pinfunction "1_1") (pintype "passive"))
      (node (ref "R109") (pin "2") (pinfunction "2_2") (pintype "passive"))
      (node (ref "R110") (pin "2") (pinfunction "2_2") (pintype "passive"))
      (node (ref "R111") (pin "2") (pinfunction "2_2") (pintype "passive"))
      (node (ref "R112") (pin "2") (pinfunction "2_2") (pintype "passive"))
      (node (ref "R114") (pin "2") (pinfunction "2_2") (pintype "passive"))
      (node (ref "R191") (pin "2") (pinfunction "2_2") (pintype "passive"))
      (node (ref "R195") (pin "2") (pinfunction "2_2") (pintype "passive"))
      (node (ref "R233") (pin "2") (pinfunction "2_2") (pintype "passive"))
      (node (ref "R318") (pin "2") (pinfunction "2_2") (pintype "passive"))
      (node (ref "R319") (pin "1") (pinfunction "1_1") (pintype "passive"))
      (node (ref "U38") (pin "28") (pinfunction "DVDD_RG_28") (pintype "power_in"))
      (node (ref "U38") (pin "29") (pinfunction "DVDD33_29") (pintype "power_in"))
    )
    (net (code "37") (name "GND") (class "Default")
      (node (ref "C103") (pin "1") (pinfunction "1_1") (pintype "passive"))
      (node (ref "C104") (pin "1") (pinfunction "1_1") (pintype "passive"))
      (node (ref "C109") (pin "1") (pinfunction "1_1") (pintype "passive"))
      (node (ref "C111") (pin "1") (pinfunction "1_1") (pintype "passive"))
      (node (ref "C120") (pin "1") (pinfunction "1_1") (pintype "passive"))
      (node (ref "C123") (pin "1") (pinfunction "1_1") (pintype "passive"))
      (node (ref "C134") (pin "1") (pinfunction "1_1") (pintype "passive"))
      (node (ref "C137") (pin "1") (pinfunction "1_1") (pintype "passive"))
      (node (ref "C141") (pin "1") (pinfunction "1_1") (pintype "passive"))
      (node (ref "C152") (pin "1") (pinfunction "1_1") (pintype "passive"))
      (node (ref "C280") (pin "2") (pinfunction "2_2") (pintype "passive"))
      (node (ref "C288") (pin "1") (pinfunction "1_1") (pintype "passive"))
      (node (ref "C295") (pin "1") (pinfunction "1_1") (pintype "passive"))
      (node (ref "C296") (pin "1") (pinfunction "1_1") (pintype "passive"))
      (node (ref "C302") (pin "1") (pinfunction "1_1") (pintype "passive"))
      (node (ref "C306") (pin "1") (pinfunction "1_1") (pintype "passive"))
      (node (ref "C309") (pin "1") (pinfunction "1_1") (pintype "passive"))
      (node (ref "C314") (pin "1") (pinfunction "1_1") (pintype "passive"))
      (node (ref "C317") (pin "1") (pinfunction "1_1") (pintype "passive"))
      (node (ref "C322") (pin "1") (pinfunction "1_1") (pintype "passive"))
      (node (ref "C323") (pin "1") (pinfunction "1_1") (pintype "passive"))
      (node (ref "C332") (pin "1") (pinfunction "1_1") (pintype "passive"))
      (node (ref "CN16") (pin "15") (pinfunction "GND_15") (pintype "power_in"))
      (node (ref "CN16") (pin "16") (pinfunction "GND_16") (pintype "power_in"))
      (node (ref "R113") (pin "1") (pinfunction "1_1") (pintype "passive"))
      (node (ref "R126") (pin "2") (pinfunction "2_2") (pintype "passive"))
      (node (ref "R158") (pin "1") (pinfunction "1_1") (pintype "passive"))
      (node (ref "R199") (pin "2") (pinfunction "2_2") (pintype "passive"))
      (node (ref "R234") (pin "1") (pinfunction "1_1") (pintype "passive"))
      (node (ref "R292") (pin "1") (pinfunction "1_1") (pintype "passive"))
      (node (ref "R293") (pin "1") (pinfunction "1_1") (pintype "passive"))
      (node (ref "R303") (pin "1") (pinfunction "1_1") (pintype "passive"))
      (node (ref "R304") (pin "1") (pinfunction "1_1") (pintype "passive"))
      (node (ref "R305") (pin "1") (pinfunction "1_1") (pintype "passive"))
      (node (ref "R322") (pin "1") (pinfunction "1_1") (pintype "passive"))
      (node (ref "U38") (pin "41") (pinfunction "E-PAD_41") (pintype "power_in"))
      (node (ref "X4") (pin "2") (pinfunction "2_2") (pintype "passive"))
      (node (ref "X4") (pin "4") (pinfunction "4_4") (pintype "passive"))
    )
    (net (code "38") (name "Net-(C134-Pad2)") (class "Default")
      (node (ref "C134") (pin "2") (pinfunction "2_2") (pintype "passive"))
      (node (ref "R182") (pin "1") (pinfunction "1_1") (pintype "passive"))
      (node (ref "X4") (pin "1") (pinfunction "1_1") (pintype "passive"))
    )
    (net (code "39") (name "Net-(C137-Pad2)") (class "Default")
      (node (ref "C137") (pin "2") (pinfunction "2_2") (pintype "passive"))
      (node (ref "R188") (pin "1") (pinfunction "1_1") (pintype "passive"))
      (node (ref "X4") (pin "3") (pinfunction "3_3") (pintype "passive"))
    )
    (net (code "40") (name "Net-(CN16-CT1)") (class "Default")
      (node (ref "C152") (pin "2") (pinfunction "2_2") (pintype "passive"))
      (node (ref "CN16") (pin "5") (pinfunction "CT1_5") (pintype "passive"))
      (node (ref "CN16") (pin "6") (pinfunction "CT2_6") (pintype "passive"))
    )
    (net (code "41") (name "Net-(CN16-GA)") (class "Default")
      (node (ref "CN16") (pin "11") (pinfunction "GA_11") (pintype "passive"))
      (node (ref "R233") (pin "1") (pinfunction "1_1") (pintype "passive"))
    )
    (net (code "42") (name "Net-(CN16-GC)") (class "Default")
      (node (ref "CN16") (pin "12") (pinfunction "GC_12") (pintype "passive"))
      (node (ref "R319") (pin "2") (pinfunction "2_2") (pintype "passive"))
      (node (ref "U38") (pin "32") (pinfunction "LED0_CFG_EXT_32") (pintype "bidirectional"))
    )
    (net (code "43") (name "Net-(CN16-YA)") (class "Default")
      (node (ref "CN16") (pin "13") (pinfunction "YA_13") (pintype "passive"))
      (node (ref "R322") (pin "2") (pinfunction "2_2") (pintype "passive"))
      (node (ref "U38") (pin "33") (pinfunction "LED1_CFG_LD0_33") (pintype "bidirectional"))
    )
    (net (code "44") (name "Net-(CN16-YC)") (class "Default")
      (node (ref "CN16") (pin "14") (pinfunction "YC_14") (pintype "passive"))
      (node (ref "R234") (pin "2") (pinfunction "2_2") (pintype "passive"))
    )
    (net (code "45") (name "Net-(LD7-Pad2)") (class "Default")
      (node (ref "LD7") (pin "2") (pintype "passive"))
      (node (ref "R126") (pin "1") (pinfunction "1_1") (pintype "passive"))
    )
    (net (code "46") (name "Net-(U38-CLKOUT)") (class "Default")
      (node (ref "R176") (pin "2") (pinfunction "2_2") (pintype "passive"))
      (node (ref "U38") (pin "35") (pinfunction "CLKOUT_35") (pintype "output"))
    )
    (net (code "47") (name "Net-(U38-LED2_CFG_LDO1)") (class "Default")
      (node (ref "LD7") (pin "1") (pintype "passive"))
      (node (ref "R158") (pin "2") (pinfunction "2_2") (pintype "passive"))
      (node (ref "U38") (pin "34") (pinfunction "LED2_CFG_LDO1_34") (pintype "output"))
    )
    (net (code "48") (name "Net-(U38-REG_OUT)") (class "Default")
      (node (ref "LE1") (pin "1") (pinfunction "1_1") (pintype "passive"))
      (node (ref "U38") (pin "30") (pinfunction "REG_OUT_30") (pintype "output"))
    )
    (net (code "49") (name "Net-(U38-RSET)") (class "Default")
      (node (ref "R199") (pin "1") (pinfunction "1_1") (pintype "passive"))
      (node (ref "U38") (pin "39") (pinfunction "RSET_39") (pintype "output"))
    )
    (net (code "50") (name "Net-(U38-RXCLK_PHYAD1)") (class "Default")
      (node (ref "R135") (pin "2") (pinfunction "2_2") (pintype "passive"))
      (node (ref "U38") (pin "27") (pinfunction "RXCLK_PHYAD1_27") (pintype "passive"))
    )
    (net (code "51") (name "Net-(U38-RXCTL_PHYAD2)") (class "Default")
      (node (ref "R136") (pin "2") (pinfunction "2_2") (pintype "passive"))
      (node (ref "U38") (pin "26") (pinfunction "RXCTL_PHYAD2_26") (pintype "passive"))
    )
    (net (code "52") (name "Net-(U38-RXD0_RXDLY)") (class "Default")
      (node (ref "R137") (pin "2") (pinfunction "2_2") (pintype "passive"))
      (node (ref "U38") (pin "25") (pinfunction "RXD0_RXDLY_25") (pintype "output"))
    )
    (net (code "53") (name "Net-(U38-RXD1_TXDLY)") (class "Default")
      (node (ref "R138") (pin "2") (pinfunction "2_2") (pintype "passive"))
      (node (ref "U38") (pin "24") (pinfunction "RXD1_TXDLY_24") (pintype "output"))
    )
    (net (code "54") (name "Net-(U38-RXD2_PLLOFF)") (class "Default")
      (node (ref "R139") (pin "2") (pinfunction "2_2") (pintype "passive"))
      (node (ref "U38") (pin "23") (pinfunction "RXD2_PLLOFF_23") (pintype "output"))
    )
    (net (code "55") (name "Net-(U38-RXD3_PHYAD0)") (class "Default")
      (node (ref "R140") (pin "2") (pinfunction "2_2") (pintype "passive"))
      (node (ref "U38") (pin "22") (pinfunction "RXD3_PHYAD0_22") (pintype "output"))
    )
    (net (code "56") (name "Net-(U38-TXCLK)") (class "Default")
      (node (ref "R161") (pin "2") (pinfunction "2_2") (pintype "passive"))
      (node (ref "U38") (pin "20") (pinfunction "TXCLK_20") (pintype "input"))
    )
    (net (code "57") (name "Net-(U38-TXCTL)") (class "Default")
      (node (ref "R164") (pin "2") (pinfunction "2_2") (pintype "passive"))
      (node (ref "U38") (pin "19") (pinfunction "TXCTL_19") (pintype "input"))
    )
    (net (code "58") (name "Net-(U38-TXD0)") (class "Default")
      (node (ref "R167") (pin "2") (pinfunction "2_2") (pintype "passive"))
      (node (ref "U38") (pin "18") (pinfunction "TXD0_18") (pintype "input"))
    )
    (net (code "59") (name "Net-(U38-TXD1)") (class "Default")
      (node (ref "R173") (pin "2") (pinfunction "2_2") (pintype "passive"))
      (node (ref "U38") (pin "17") (pinfunction "TXD1_17") (pintype "input"))
    )
    (net (code "60") (name "Net-(U38-TXD2)") (class "Default")
      (node (ref "R178") (pin "2") (pinfunction "2_2") (pintype "passive"))
      (node (ref "U38") (pin "16") (pinfunction "TXD2_16") (pintype "input"))
    )
    (net (code "61") (name "Net-(U38-TXD3)") (class "Default")
      (node (ref "R185") (pin "2") (pinfunction "2_2") (pintype "passive"))
      (node (ref "U38") (pin "15") (pinfunction "TXD3_15") (pintype "input"))
    )
    (net (code "62") (name "Net-(U38-XTAL_IN)") (class "Default")
      (node (ref "R182") (pin "2") (pinfunction "2_2") (pintype "passive"))
      (node (ref "U38") (pin "36") (pinfunction "XTAL_IN_36") (pintype "input"))
    )
    (net (code "63") (name "Net-(U38-XTAL_OUT_EXT_CLK)") (class "Default")
      (node (ref "R188") (pin "2") (pinfunction "2_2") (pintype "passive"))
      (node (ref "R196") (pin "2") (pinfunction "2_2") (pintype "passive"))
      (node (ref "U38") (pin "37") (pinfunction "XTAL_OUT_EXT_CLK_37") (pintype "output"))
    )
  )
)
